# rejestrator_trasy.net
KiCad netlist of a schematic drawn in Altium Designer
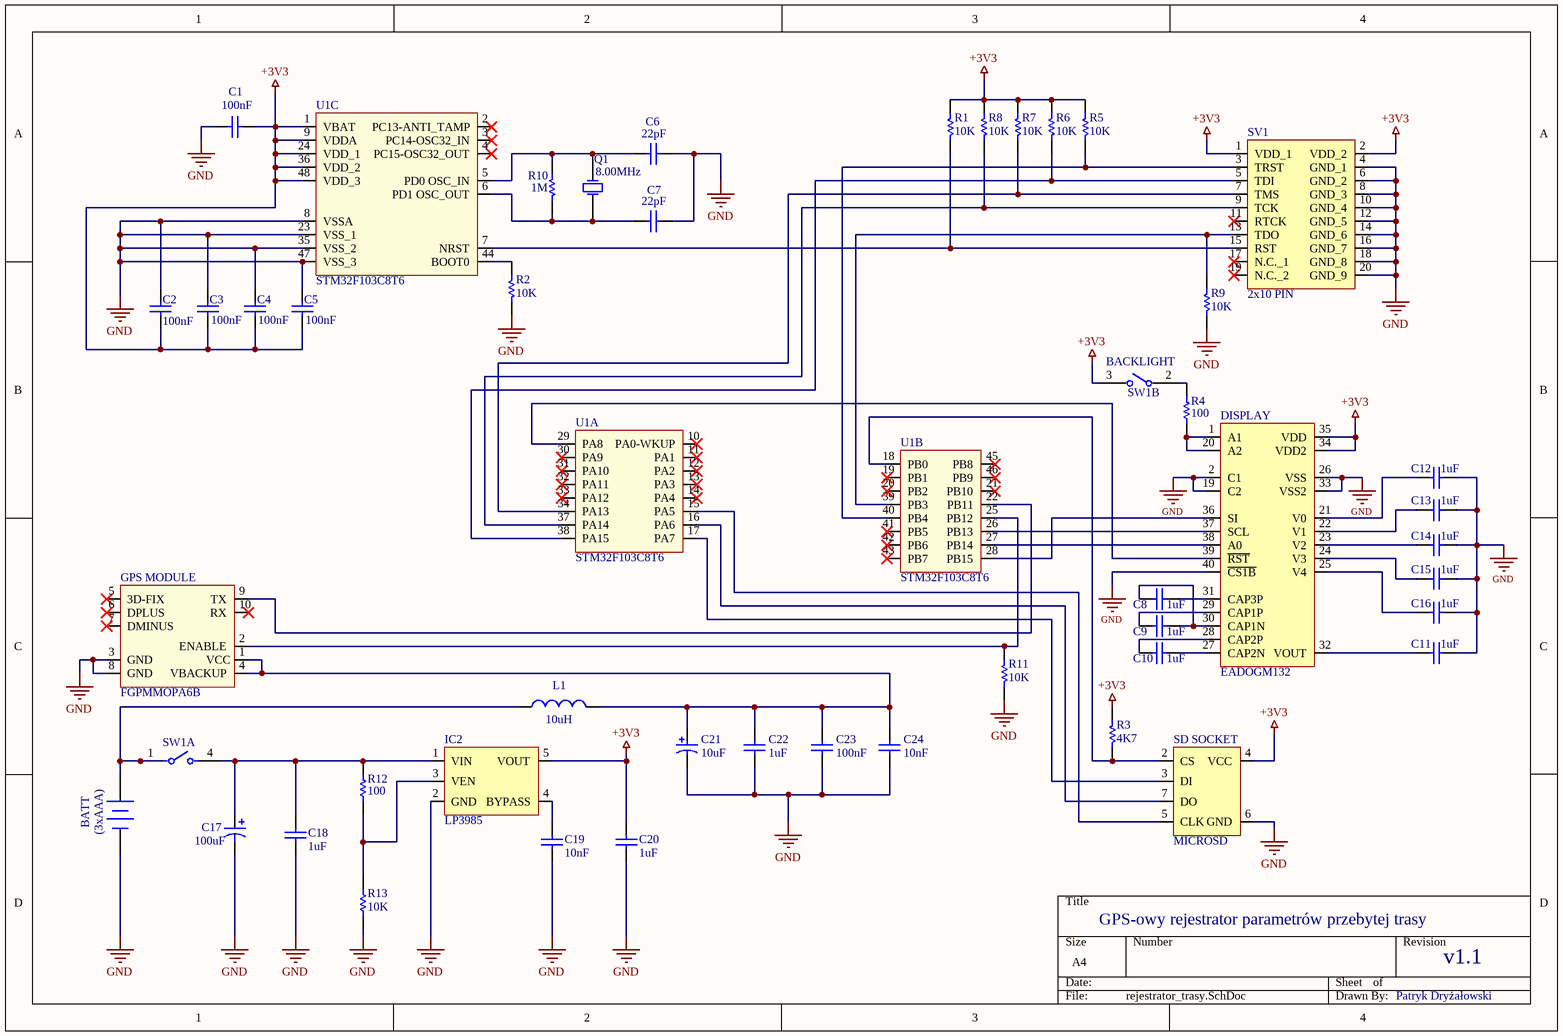
[diagram p0: rejestrator_trasy.SchDoc]

(export (version "E")
  (design (tool "Eeschema 10.0.6"))
  (components
    (comp (ref "2x10 PIN")
      (value "SV1")
      (footprint "GOLDPIN 2x10 SMD")
      (libsource (lib "PD_SCH_19Z") (part "SV1"))
    )
    (comp (ref "BATT")
      (value "(3xAAA)")
      (footprint "BAT-2")
      (description "Multicell Battery")
      (fields (field (name "PUBLISHER") "Altium Limited"))
      (libsource (lib "Miscellaneous Devices") (part "Battery"))
    )
    (comp (ref "C1")
      (value "100nF")
      (footprint "CAPC0805(2012)75_N")
      (description "CAP 100nF 25V -20% to +80% 0805 (2012 Metric) Thickness 0.75mm SMD")
      (fields (field (name "TOLERANCE") "-20% to +80%") (field (name "Comment") "CAP 100nF 25V 0805(2012)"))
      (libsource (lib "Altium Content Vault") (part "CAP"))
    )
    (comp (ref "C2")
      (value "100nF")
      (footprint "CAPC0805(2012)75_N")
      (description "CAP 100nF 25V -20% to +80% 0805 (2012 Metric) Thickness 0.75mm SMD")
      (fields (field (name "TOLERANCE") "-20% to +80%") (field (name "Comment") "CAP 100nF 25V 0805(2012)"))
      (libsource (lib "Altium Content Vault") (part "CAP"))
    )
    (comp (ref "C3")
      (value "100nF")
      (footprint "CAPC0805(2012)75_N")
      (description "CAP 100nF 25V -20% to +80% 0805 (2012 Metric) Thickness 0.75mm SMD")
      (fields (field (name "TOLERANCE") "-20% to +80%") (field (name "Comment") "CAP 100nF 25V 0805(2012)"))
      (libsource (lib "Altium Content Vault") (part "CAP"))
    )
    (comp (ref "C4")
      (value "100nF")
      (footprint "CAPC0805(2012)75_N")
      (description "CAP 100nF 25V -20% to +80% 0805 (2012 Metric) Thickness 0.75mm SMD")
      (fields (field (name "TOLERANCE") "-20% to +80%") (field (name "Comment") "CAP 100nF 25V 0805(2012)"))
      (libsource (lib "Altium Content Vault") (part "CAP"))
    )
    (comp (ref "C5")
      (value "100nF")
      (footprint "CAPC0805(2012)75_N")
      (description "CAP 100nF 25V -20% to +80% 0805 (2012 Metric) Thickness 0.75mm SMD")
      (fields (field (name "TOLERANCE") "-20% to +80%") (field (name "Comment") "CAP 100nF 25V 0805(2012)"))
      (libsource (lib "Altium Content Vault") (part "CAP"))
    )
    (comp (ref "C6")
      (value "22pF")
      (footprint "CAPC0805(2012)100_M")
      (description "CAP 22pF 10V ±20% 0805 (2012 Metric) Thickness 1mm SMD")
      (fields (field (name "TOLERANCE") "Â±20%") (field (name "Comment") "CAP 22pF 10V 0805(2012)"))
      (libsource (lib "Altium Content Vault") (part "CAP"))
    )
    (comp (ref "C7")
      (value "22pF")
      (footprint "CAPC0805(2012)100_M")
      (description "CAP 22pF 10V ±20% 0805 (2012 Metric) Thickness 1mm SMD")
      (fields (field (name "TOLERANCE") "Â±20%") (field (name "Comment") "CAP 22pF 10V 0805(2012)"))
      (libsource (lib "Altium Content Vault") (part "CAP"))
    )
    (comp (ref "C8")
      (value "1uF")
      (footprint "CAPC0805(2012)145_M")
      (description "CAP 1uF 10V ±20% 0805 (2012 Metric) Thickness 1.45mm SMD")
      (fields (field (name "TOLERANCE") "Â±20%") (field (name "Comment") "CAP 1uF 10V 0805(2012)"))
      (libsource (lib "Altium Content Vault") (part "CAP"))
    )
    (comp (ref "C9")
      (value "1uF")
      (footprint "CAPC0805(2012)145_M")
      (description "CAP 1uF 10V ±20% 0805 (2012 Metric) Thickness 1.45mm SMD")
      (fields (field (name "TOLERANCE") "Â±20%") (field (name "Comment") "CAP 1uF 10V 0805(2012)"))
      (libsource (lib "Altium Content Vault") (part "CAP"))
    )
    (comp (ref "C10")
      (value "1uF")
      (footprint "CAPC0805(2012)145_M")
      (description "CAP 1uF 10V ±20% 0805 (2012 Metric) Thickness 1.45mm SMD")
      (fields (field (name "TOLERANCE") "Â±20%") (field (name "Comment") "CAP 1uF 10V 0805(2012)"))
      (libsource (lib "Altium Content Vault") (part "CAP"))
    )
    (comp (ref "C11")
      (value "1uF")
      (footprint "CAPC0805(2012)145_M")
      (description "CAP 1uF 10V ±20% 0805 (2012 Metric) Thickness 1.45mm SMD")
      (fields (field (name "TOLERANCE") "Â±20%") (field (name "Comment") "CAP 1uF 10V 0805(2012)"))
      (libsource (lib "Altium Content Vault") (part "CAP"))
    )
    (comp (ref "C12")
      (value "1uF")
      (footprint "CAPC0805(2012)145_M")
      (description "CAP 1uF 10V ±20% 0805 (2012 Metric) Thickness 1.45mm SMD")
      (fields (field (name "TOLERANCE") "Â±20%") (field (name "Comment") "CAP 1uF 10V 0805(2012)"))
      (libsource (lib "Altium Content Vault") (part "CAP"))
    )
    (comp (ref "C13")
      (value "1uF")
      (footprint "CAPC0805(2012)145_M")
      (description "CAP 1uF 10V ±20% 0805 (2012 Metric) Thickness 1.45mm SMD")
      (fields (field (name "TOLERANCE") "Â±20%") (field (name "Comment") "CAP 1uF 10V 0805(2012)"))
      (libsource (lib "Altium Content Vault") (part "CAP"))
    )
    (comp (ref "C14")
      (value "1uF")
      (footprint "CAPC0805(2012)145_M")
      (description "CAP 1uF 10V ±20% 0805 (2012 Metric) Thickness 1.45mm SMD")
      (fields (field (name "TOLERANCE") "Â±20%") (field (name "Comment") "CAP 1uF 10V 0805(2012)"))
      (libsource (lib "Altium Content Vault") (part "CAP"))
    )
    (comp (ref "C15")
      (value "1uF")
      (footprint "CAPC0805(2012)145_M")
      (description "CAP 1uF 10V ±20% 0805 (2012 Metric) Thickness 1.45mm SMD")
      (fields (field (name "TOLERANCE") "Â±20%") (field (name "Comment") "CAP 1uF 10V 0805(2012)"))
      (libsource (lib "Altium Content Vault") (part "CAP"))
    )
    (comp (ref "C16")
      (value "1uF")
      (footprint "CAPC0805(2012)145_M")
      (description "CAP 1uF 10V ±20% 0805 (2012 Metric) Thickness 1.45mm SMD")
      (fields (field (name "TOLERANCE") "Â±20%") (field (name "Comment") "CAP 1uF 10V 0805(2012)"))
      (libsource (lib "Altium Content Vault") (part "CAP"))
    )
    (comp (ref "C17")
      (value "100uF")
      (footprint "C0805")
      (description "Polarized Capacitor (Surface Mount)")
      (fields (field (name "Comment") "Cap Pol3") (field (name "PUBLISHER") "Altium Limited"))
      (libsource (lib "Miscellaneous Devices") (part "Cap Pol3"))
    )
    (comp (ref "C18")
      (value "1uF")
      (footprint "CAPC0805(2012)145_M")
      (description "CAP 1uF 10V ±20% 0805 (2012 Metric) Thickness 1.45mm SMD")
      (fields (field (name "TOLERANCE") "Â±20%") (field (name "Comment") "CAP 1uF 10V 0805(2012)"))
      (libsource (lib "Altium Content Vault") (part "CAP"))
    )
    (comp (ref "C19")
      (value "10nF")
      (footprint "CAPC0805(2012)75_N")
      (description "CAP 10nF 16V ±20% 0805 (2012 Metric) Thickness 0.75mm SMD")
      (fields (field (name "TOLERANCE") "Â±20%") (field (name "Comment") "CAP 10nF 16V 0805(2012)"))
      (libsource (lib "Altium Content Vault") (part "CAP"))
    )
    (comp (ref "C20")
      (value "1uF")
      (footprint "CAPC0805(2012)145_M")
      (description "CAP 1uF 10V ±20% 0805 (2012 Metric) Thickness 1.45mm SMD")
      (fields (field (name "TOLERANCE") "Â±20%") (field (name "Comment") "CAP 1uF 10V 0805(2012)"))
      (libsource (lib "Altium Content Vault") (part "CAP"))
    )
    (comp (ref "C21")
      (value "ECA1HM100")
      (footprint "CAPPR55-200-1100X500X1200")
      (description "Aluminum Electrolytic Capacitor, 10 uF, +/- 20%, 50 V, -40 to 85 degC, 2-Pin THD, RoHS, Bulk")
      (fields
        (field (name "MANUFACTURER") "Panasonic")
        (field (name "CAPACITANCE") "10uF")
        (field (name "TOLERANCE") "20%")
      )
      (libsource (lib "Altium Content Vault") (part "CAP-P-2"))
    )
    (comp (ref "C22")
      (value "1uF")
      (footprint "CAPC0805(2012)145_M")
      (description "CAP 1uF 10V ±20% 0805 (2012 Metric) Thickness 1.45mm SMD")
      (fields (field (name "TOLERANCE") "Â±20%") (field (name "Comment") "CAP 1uF 10V 0805(2012)"))
      (libsource (lib "Altium Content Vault") (part "CAP"))
    )
    (comp (ref "C23")
      (value "100nF")
      (footprint "CAPC0805(2012)75_N")
      (description "CAP 100nF 25V -20% to +80% 0805 (2012 Metric) Thickness 0.75mm SMD")
      (fields (field (name "TOLERANCE") "-20% to +80%") (field (name "Comment") "CAP 100nF 25V 0805(2012)"))
      (libsource (lib "Altium Content Vault") (part "CAP"))
    )
    (comp (ref "C24")
      (value "10nF")
      (footprint "CAPC0805(2012)75_N")
      (description "CAP 10nF 16V ±20% 0805 (2012 Metric) Thickness 0.75mm SMD")
      (fields (field (name "TOLERANCE") "Â±20%") (field (name "Comment") "CAP 10nF 16V 0805(2012)"))
      (libsource (lib "Altium Content Vault") (part "CAP"))
    )
    (comp (ref "DISPLAY")
      (value "EADOGM132")
      (footprint "EA DOGM132")
      (libsource (lib "PD_SCH_19Z") (part "EA DOGM132"))
    )
    (comp (ref "GPS MODULE")
      (value "FGPMMOPA6B")
      (footprint "GTPA010")
      (libsource (lib "PD_SCH_19Z") (part "FGPMMOPA6B"))
    )
    (comp (ref "IC2") (value "LP3985") (footprint "SOT-23") (libsource (lib "PD_SCH_19Z") (part "LP3985")))
    (comp (ref "L1")
      (value "BRC2012T2R2MD")
      (footprint "INDC2013X140X50LL20T20")
      (fields
        (field (name "TOLERANCE") "±20%")
        (field (name "INDUCTANCE") "10uH")
        (field (name "MANUFACTURER") "Taiyo Yuden")
      )
      (libsource (lib "Altium Content Vault") (part "IND-2"))
    )
    (comp (ref "Q1")
      (value "Quartz")
      (footprint "TXC-9C-2_V")
      (fields
        (field (name "PARTNUMBER") "9C-3.6864MBBK-T")
        (field (name "MANUFACTURER") "TXC")
        (field (name "FREQUENCY") "8.00MHz")
      )
      (libsource (lib "Altium Content Vault") (part "TXC-XTAL_1-2-2"))
    )
    (comp (ref "R1")
      (value "10K")
      (footprint "RESC0805(2012)_L")
      (description "10K 0.125W 5% 0805 (2012 Metric)  SMD")
      (fields (field (name "POWER") "0.125 W") (field (name "TOLERANCE") "5 %"))
      (libsource (lib "Altium Content Vault") (part "RES"))
    )
    (comp (ref "R2")
      (value "10K")
      (footprint "RESC0805(2012)_L")
      (description "10K 0.125W 5% 0805 (2012 Metric)  SMD")
      (fields (field (name "POWER") "0.125 W") (field (name "TOLERANCE") "5 %"))
      (libsource (lib "Altium Content Vault") (part "RES"))
    )
    (comp (ref "R3")
      (value "4K7")
      (footprint "RESC0805(2012)_N")
      (description "4K7 0.125W 5% 0805 (2012 Metric)  SMD")
      (fields (field (name "POWER") "0.125 W") (field (name "TOLERANCE") "5 %"))
      (libsource (lib "Altium Content Vault") (part "RES"))
    )
    (comp (ref "R4")
      (value "100")
      (footprint "RESC0805(2012)_M")
      (description "100R 0.125W 5% 0805 (2012 Metric)  SMD")
      (fields (field (name "TOLERANCE") "5 %") (field (name "POWER") "0.125 W"))
      (libsource (lib "Altium Content Vault") (part "RES"))
    )
    (comp (ref "R5")
      (value "10K")
      (footprint "RESC0805(2012)_L")
      (description "10K 0.125W 5% 0805 (2012 Metric)  SMD")
      (fields (field (name "POWER") "0.125 W") (field (name "TOLERANCE") "5 %"))
      (libsource (lib "Altium Content Vault") (part "RES"))
    )
    (comp (ref "R6")
      (value "10K")
      (footprint "RESC0805(2012)_L")
      (description "10K 0.125W 5% 0805 (2012 Metric)  SMD")
      (fields (field (name "POWER") "0.125 W") (field (name "TOLERANCE") "5 %"))
      (libsource (lib "Altium Content Vault") (part "RES"))
    )
    (comp (ref "R7")
      (value "10K")
      (footprint "RESC0805(2012)_L")
      (description "10K 0.125W 5% 0805 (2012 Metric)  SMD")
      (fields (field (name "POWER") "0.125 W") (field (name "TOLERANCE") "5 %"))
      (libsource (lib "Altium Content Vault") (part "RES"))
    )
    (comp (ref "R8")
      (value "10K")
      (footprint "RESC0805(2012)_L")
      (description "10K 0.125W 5% 0805 (2012 Metric)  SMD")
      (fields (field (name "POWER") "0.125 W") (field (name "TOLERANCE") "5 %"))
      (libsource (lib "Altium Content Vault") (part "RES"))
    )
    (comp (ref "R9")
      (value "10K")
      (footprint "RESC0805(2012)_L")
      (description "10K 0.125W 5% 0805 (2012 Metric)  SMD")
      (fields (field (name "POWER") "0.125 W") (field (name "TOLERANCE") "5 %"))
      (libsource (lib "Altium Content Vault") (part "RES"))
    )
    (comp (ref "R10")
      (value "1M")
      (footprint "RESC0805(2012)_L")
      (description "1M 0.125W 5% 0805 (2012 Metric)  SMD")
      (fields (field (name "TOLERANCE") "5 %") (field (name "POWER") "0.125 W"))
      (libsource (lib "Altium Content Vault") (part "RES"))
    )
    (comp (ref "R11")
      (value "10K")
      (footprint "RESC0805(2012)_L")
      (description "10K 0.125W 5% 0805 (2012 Metric)  SMD")
      (fields (field (name "POWER") "0.125 W") (field (name "TOLERANCE") "5 %"))
      (libsource (lib "Altium Content Vault") (part "RES"))
    )
    (comp (ref "R12")
      (value "100")
      (footprint "RESC0805(2012)_M")
      (description "100R 0.125W 5% 0805 (2012 Metric)  SMD")
      (fields (field (name "TOLERANCE") "5 %") (field (name "POWER") "0.125 W"))
      (libsource (lib "Altium Content Vault") (part "RES"))
    )
    (comp (ref "R13")
      (value "10K")
      (footprint "RESC0805(2012)_L")
      (description "10K 0.125W 5% 0805 (2012 Metric)  SMD")
      (fields (field (name "POWER") "0.125 W") (field (name "TOLERANCE") "5 %"))
      (libsource (lib "Altium Content Vault") (part "RES"))
    )
    (comp (ref "SD SOCKET")
      (value "MICROSD")
      (footprint "SD CONN")
      (libsource (lib "PD_SCH_19Z") (part "MICROSD"))
    )
    (comp (ref "SW1")
      (value "1825057-1")
      (footprint "TE_Connectivity_1825057-1_MFG")
      (description "SWITCH SLIDE DIP SPST 100MA 24V")
      (fields (field (name "PART NUMBER") "1825057-1") (field (name "MANUFACTURER") "TE Connectivity"))
      (libsource (lib "Altium Content Vault") (part "1825057-1"))
    )
    (comp (ref "U1")
      (value "STM32F103C8T6")
      (footprint "LQFP48")
      (libsource (lib "") (part "STM32F103C8T6_2"))
    )
  )
  (nets
    (net (code "1") (name "+3V3") (class "Default")
      (node (ref "2x10 PIN") (pin "1") (pinfunction "VDD_1_1") (pintype "passive"))
      (node (ref "2x10 PIN") (pin "2") (pinfunction "VDD_2_2") (pintype "passive"))
      (node (ref "C1") (pin "2") (pinfunction "2_2") (pintype "passive"))
      (node (ref "C2") (pin "1") (pinfunction "1_1") (pintype "passive"))
      (node (ref "C20") (pin "2") (pinfunction "2_2") (pintype "passive"))
      (node (ref "C3") (pin "1") (pinfunction "1_1") (pintype "passive"))
      (node (ref "C4") (pin "1") (pinfunction "1_1") (pintype "passive"))
      (node (ref "C5") (pin "1") (pinfunction "1_1") (pintype "passive"))
      (node (ref "DISPLAY") (pin "34") (pinfunction "VDD2_34") (pintype "passive"))
      (node (ref "DISPLAY") (pin "35") (pinfunction "VDD_35") (pintype "passive"))
      (node (ref "IC2") (pin "5") (pinfunction "VOUT_5") (pintype "passive"))
      (node (ref "R1") (pin "2") (pinfunction "2_2") (pintype "passive"))
      (node (ref "R3") (pin "2") (pinfunction "2_2") (pintype "passive"))
      (node (ref "R5") (pin "2") (pinfunction "2_2") (pintype "passive"))
      (node (ref "R6") (pin "2") (pinfunction "2_2") (pintype "passive"))
      (node (ref "R7") (pin "2") (pinfunction "2_2") (pintype "passive"))
      (node (ref "R8") (pin "2") (pinfunction "2_2") (pintype "passive"))
      (node (ref "SD SOCKET") (pin "4") (pinfunction "VCC_4") (pintype "passive"))
      (node (ref "SW1") (pin "3") (pinfunction "3_3") (pintype "passive"))
      (node (ref "U1") (pin "1") (pinfunction "VBAT_1") (pintype "passive"))
      (node (ref "U1") (pin "24") (pinfunction "VDD_1_24") (pintype "passive"))
      (node (ref "U1") (pin "36") (pinfunction "VDD_2_36") (pintype "passive"))
      (node (ref "U1") (pin "48") (pinfunction "VDD_3_48") (pintype "passive"))
      (node (ref "U1") (pin "9") (pinfunction "VDDA_9") (pintype "passive"))
    )
    (net (code "2") (name "GND") (class "Default")
      (node (ref "2x10 PIN") (pin "10") (pinfunction "GND_4_10") (pintype "passive"))
      (node (ref "2x10 PIN") (pin "12") (pinfunction "GND_5_12") (pintype "passive"))
      (node (ref "2x10 PIN") (pin "14") (pinfunction "GND_6_14") (pintype "passive"))
      (node (ref "2x10 PIN") (pin "16") (pinfunction "GND_7_16") (pintype "passive"))
      (node (ref "2x10 PIN") (pin "18") (pinfunction "GND_8_18") (pintype "passive"))
      (node (ref "2x10 PIN") (pin "20") (pinfunction "GND_9_20") (pintype "passive"))
      (node (ref "2x10 PIN") (pin "4") (pinfunction "GND_1_4") (pintype "passive"))
      (node (ref "2x10 PIN") (pin "6") (pinfunction "GND_2_6") (pintype "passive"))
      (node (ref "2x10 PIN") (pin "8") (pinfunction "GND_3_8") (pintype "passive"))
      (node (ref "BATT") (pin "2") (pinfunction "-_2") (pintype "passive"))
      (node (ref "C1") (pin "1") (pinfunction "1_1") (pintype "passive"))
      (node (ref "C11") (pin "2") (pinfunction "2_2") (pintype "passive"))
      (node (ref "C12") (pin "2") (pinfunction "2_2") (pintype "passive"))
      (node (ref "C13") (pin "2") (pinfunction "2_2") (pintype "passive"))
      (node (ref "C14") (pin "2") (pinfunction "2_2") (pintype "passive"))
      (node (ref "C15") (pin "2") (pinfunction "2_2") (pintype "passive"))
      (node (ref "C16") (pin "2") (pinfunction "2_2") (pintype "passive"))
      (node (ref "C17") (pin "2") (pinfunction "2_2") (pintype "passive"))
      (node (ref "C18") (pin "1") (pinfunction "1_1") (pintype "passive"))
      (node (ref "C19") (pin "1") (pinfunction "1_1") (pintype "passive"))
      (node (ref "C2") (pin "2") (pinfunction "2_2") (pintype "passive"))
      (node (ref "C20") (pin "1") (pinfunction "1_1") (pintype "passive"))
      (node (ref "C21") (pin "2") (pinfunction "2_2") (pintype "passive"))
      (node (ref "C22") (pin "1") (pinfunction "1_1") (pintype "passive"))
      (node (ref "C23") (pin "1") (pinfunction "1_1") (pintype "passive"))
      (node (ref "C24") (pin "1") (pinfunction "1_1") (pintype "passive"))
      (node (ref "C3") (pin "2") (pinfunction "2_2") (pintype "passive"))
      (node (ref "C4") (pin "2") (pinfunction "2_2") (pintype "passive"))
      (node (ref "C5") (pin "2") (pinfunction "2_2") (pintype "passive"))
      (node (ref "C6") (pin "1") (pinfunction "1_1") (pintype "passive"))
      (node (ref "C7") (pin "1") (pinfunction "1_1") (pintype "passive"))
      (node (ref "DISPLAY") (pin "19") (pinfunction "C2_19") (pintype "passive"))
      (node (ref "DISPLAY") (pin "2") (pinfunction "C1_2") (pintype "passive"))
      (node (ref "DISPLAY") (pin "26") (pinfunction "VSS_26") (pintype "passive"))
      (node (ref "DISPLAY") (pin "33") (pinfunction "VSS2_33") (pintype "passive"))
      (node (ref "DISPLAY") (pin "40") (pinfunction "~{CS1B}_40") (pintype "passive"))
      (node (ref "GPS MODULE") (pin "3") (pinfunction "GND_3") (pintype "passive"))
      (node (ref "GPS MODULE") (pin "8") (pinfunction "GND_8") (pintype "passive"))
      (node (ref "IC2") (pin "2") (pinfunction "GND_2") (pintype "passive"))
      (node (ref "R11") (pin "1") (pinfunction "1_1") (pintype "passive"))
      (node (ref "R13") (pin "1") (pinfunction "1_1") (pintype "passive"))
      (node (ref "R2") (pin "1") (pinfunction "1_1") (pintype "passive"))
      (node (ref "R9") (pin "1") (pinfunction "1_1") (pintype "passive"))
      (node (ref "SD SOCKET") (pin "6") (pinfunction "GND_6") (pintype "passive"))
      (node (ref "U1") (pin "23") (pinfunction "VSS_1_23") (pintype "passive"))
      (node (ref "U1") (pin "35") (pinfunction "VSS_2_35") (pintype "passive"))
      (node (ref "U1") (pin "47") (pinfunction "VSS_3_47") (pintype "passive"))
      (node (ref "U1") (pin "8") (pinfunction "VSSA_8") (pintype "passive"))
    )
    (net (code "3") (name "Net-(2x10 PIN-RST)") (class "Default")
      (node (ref "2x10 PIN") (pin "15") (pinfunction "RST_15") (pintype "passive"))
      (node (ref "R1") (pin "1") (pinfunction "1_1") (pintype "passive"))
      (node (ref "U1") (pin "7") (pinfunction "NRST_7") (pintype "passive"))
    )
    (net (code "4") (name "Net-(2x10 PIN-TCK)") (class "Default")
      (node (ref "2x10 PIN") (pin "9") (pinfunction "TCK_9") (pintype "passive"))
      (node (ref "R8") (pin "1") (pinfunction "1_1") (pintype "passive"))
      (node (ref "U1") (pin "37") (pinfunction "PA14_37") (pintype "passive"))
    )
    (net (code "5") (name "Net-(2x10 PIN-TDI)") (class "Default")
      (node (ref "2x10 PIN") (pin "5") (pinfunction "TDI_5") (pintype "passive"))
      (node (ref "R6") (pin "1") (pinfunction "1_1") (pintype "passive"))
      (node (ref "U1") (pin "38") (pinfunction "PA15_38") (pintype "passive"))
    )
    (net (code "6") (name "Net-(2x10 PIN-TDO)") (class "Default")
      (node (ref "2x10 PIN") (pin "13") (pinfunction "TDO_13") (pintype "passive"))
      (node (ref "R9") (pin "2") (pinfunction "2_2") (pintype "passive"))
      (node (ref "U1") (pin "39") (pinfunction "PB3_39") (pintype "passive"))
    )
    (net (code "7") (name "Net-(2x10 PIN-TMS)") (class "Default")
      (node (ref "2x10 PIN") (pin "7") (pinfunction "TMS_7") (pintype "passive"))
      (node (ref "R7") (pin "1") (pinfunction "1_1") (pintype "passive"))
      (node (ref "U1") (pin "34") (pinfunction "PA13_34") (pintype "passive"))
    )
    (net (code "8") (name "Net-(2x10 PIN-TRST)") (class "Default")
      (node (ref "2x10 PIN") (pin "3") (pinfunction "TRST_3") (pintype "passive"))
      (node (ref "R5") (pin "1") (pinfunction "1_1") (pintype "passive"))
      (node (ref "U1") (pin "40") (pinfunction "PB4_40") (pintype "passive"))
    )
    (net (code "9") (name "Net-(BATT-+)") (class "Default")
      (node (ref "BATT") (pin "1") (pinfunction "+_1") (pintype "passive"))
      (node (ref "L1") (pin "1") (pinfunction "1_1") (pintype "passive"))
      (node (ref "SW1") (pin "1") (pinfunction "1_1") (pintype "passive"))
    )
    (net (code "10") (name "Net-(DISPLAY-A0)") (class "Default")
      (node (ref "DISPLAY") (pin "38") (pinfunction "A0_38") (pintype "passive"))
      (node (ref "U1") (pin "27") (pinfunction "PB14_27") (pintype "passive"))
    )
    (net (code "11") (name "Net-(DISPLAY-A1)") (class "Default")
      (node (ref "DISPLAY") (pin "1") (pinfunction "A1_1") (pintype "passive"))
      (node (ref "DISPLAY") (pin "20") (pinfunction "A2_20") (pintype "passive"))
      (node (ref "R4") (pin "1") (pinfunction "1_1") (pintype "passive"))
    )
    (net (code "12") (name "Net-(DISPLAY-CAP1N)") (class "Default")
      (node (ref "C8") (pin "1") (pinfunction "1_1") (pintype "passive"))
      (node (ref "C9") (pin "2") (pinfunction "2_2") (pintype "passive"))
      (node (ref "DISPLAY") (pin "30") (pinfunction "CAP1N_30") (pintype "passive"))
    )
    (net (code "13") (name "Net-(DISPLAY-CAP1P)") (class "Default")
      (node (ref "C9") (pin "1") (pinfunction "1_1") (pintype "passive"))
      (node (ref "DISPLAY") (pin "29") (pinfunction "CAP1P_29") (pintype "passive"))
    )
    (net (code "14") (name "Net-(DISPLAY-CAP2N)") (class "Default")
      (node (ref "C10") (pin "2") (pinfunction "2_2") (pintype "passive"))
      (node (ref "DISPLAY") (pin "27") (pinfunction "CAP2N_27") (pintype "passive"))
    )
    (net (code "15") (name "Net-(DISPLAY-CAP2P)") (class "Default")
      (node (ref "C10") (pin "1") (pinfunction "1_1") (pintype "passive"))
      (node (ref "DISPLAY") (pin "28") (pinfunction "CAP2P_28") (pintype "passive"))
    )
    (net (code "16") (name "Net-(DISPLAY-CAP3P)") (class "Default")
      (node (ref "C8") (pin "2") (pinfunction "2_2") (pintype "passive"))
      (node (ref "DISPLAY") (pin "31") (pinfunction "CAP3P_31") (pintype "passive"))
    )
    (net (code "17") (name "Net-(DISPLAY-SCL)") (class "Default")
      (node (ref "DISPLAY") (pin "37") (pinfunction "SCL_37") (pintype "passive"))
      (node (ref "U1") (pin "26") (pinfunction "PB13_26") (pintype "passive"))
    )
    (net (code "18") (name "Net-(DISPLAY-SI)") (class "Default")
      (node (ref "DISPLAY") (pin "36") (pinfunction "SI_36") (pintype "passive"))
      (node (ref "U1") (pin "28") (pinfunction "PB15_28") (pintype "passive"))
    )
    (net (code "19") (name "Net-(DISPLAY-V0)") (class "Default")
      (node (ref "C12") (pin "1") (pinfunction "1_1") (pintype "passive"))
      (node (ref "DISPLAY") (pin "21") (pinfunction "V0_21") (pintype "passive"))
    )
    (net (code "20") (name "Net-(DISPLAY-V1)") (class "Default")
      (node (ref "C13") (pin "1") (pinfunction "1_1") (pintype "passive"))
      (node (ref "DISPLAY") (pin "22") (pinfunction "V1_22") (pintype "passive"))
    )
    (net (code "21") (name "Net-(DISPLAY-V2)") (class "Default")
      (node (ref "C14") (pin "1") (pinfunction "1_1") (pintype "passive"))
      (node (ref "DISPLAY") (pin "23") (pinfunction "V2_23") (pintype "passive"))
    )
    (net (code "22") (name "Net-(DISPLAY-V3)") (class "Default")
      (node (ref "C15") (pin "1") (pinfunction "1_1") (pintype "passive"))
      (node (ref "DISPLAY") (pin "24") (pinfunction "V3_24") (pintype "passive"))
    )
    (net (code "23") (name "Net-(DISPLAY-V4)") (class "Default")
      (node (ref "C16") (pin "1") (pinfunction "1_1") (pintype "passive"))
      (node (ref "DISPLAY") (pin "25") (pinfunction "V4_25") (pintype "passive"))
    )
    (net (code "24") (name "Net-(DISPLAY-VOUT)") (class "Default")
      (node (ref "C11") (pin "1") (pinfunction "1_1") (pintype "passive"))
      (node (ref "DISPLAY") (pin "32") (pinfunction "VOUT_32") (pintype "passive"))
    )
    (net (code "25") (name "Net-(DISPLAY-~{RST})") (class "Default")
      (node (ref "DISPLAY") (pin "39") (pinfunction "~{RST}_39") (pintype "passive"))
      (node (ref "U1") (pin "29") (pinfunction "PA8_29") (pintype "passive"))
    )
    (net (code "26") (name "Net-(GPS MODULE-ENABLE)") (class "Default")
      (node (ref "GPS MODULE") (pin "2") (pinfunction "ENABLE_2") (pintype "passive"))
      (node (ref "R11") (pin "2") (pinfunction "2_2") (pintype "passive"))
      (node (ref "U1") (pin "25") (pinfunction "PB12_25") (pintype "passive"))
    )
    (net (code "27") (name "Net-(GPS MODULE-TX)") (class "Default")
      (node (ref "GPS MODULE") (pin "9") (pinfunction "TX_9") (pintype "passive"))
      (node (ref "U1") (pin "22") (pinfunction "PB11_22") (pintype "passive"))
    )
    (net (code "28") (name "Net-(GPS MODULE-VBACKUP)") (class "Default")
      (node (ref "C21") (pin "1") (pinfunction "1_1") (pintype "passive"))
      (node (ref "C22") (pin "2") (pinfunction "2_2") (pintype "passive"))
      (node (ref "C23") (pin "2") (pinfunction "2_2") (pintype "passive"))
      (node (ref "C24") (pin "2") (pinfunction "2_2") (pintype "passive"))
      (node (ref "GPS MODULE") (pin "1") (pinfunction "VCC_1") (pintype "passive"))
      (node (ref "GPS MODULE") (pin "4") (pinfunction "VBACKUP_4") (pintype "passive"))
      (node (ref "L1") (pin "2") (pinfunction "2_2") (pintype "passive"))
    )
    (net (code "29") (name "Net-(IC2-BYPASS)") (class "Default")
      (node (ref "C19") (pin "2") (pinfunction "2_2") (pintype "passive"))
      (node (ref "IC2") (pin "4") (pinfunction "BYPASS_4") (pintype "passive"))
    )
    (net (code "30") (name "Net-(IC2-VEN)") (class "Default")
      (node (ref "IC2") (pin "3") (pinfunction "VEN_3") (pintype "passive"))
      (node (ref "R12") (pin "1") (pinfunction "1_1") (pintype "passive"))
      (node (ref "R13") (pin "2") (pinfunction "2_2") (pintype "passive"))
    )
    (net (code "31") (name "Net-(IC2-VIN)") (class "Default")
      (node (ref "C17") (pin "1") (pinfunction "1_1") (pintype "passive"))
      (node (ref "C18") (pin "2") (pinfunction "2_2") (pintype "passive"))
      (node (ref "IC2") (pin "1") (pinfunction "VIN_1") (pintype "passive"))
      (node (ref "R12") (pin "2") (pinfunction "2_2") (pintype "passive"))
      (node (ref "SW1") (pin "4") (pinfunction "4_4") (pintype "passive"))
    )
    (net (code "32") (name "Net-(Q1-X1)") (class "Default")
      (node (ref "C6") (pin "2") (pinfunction "2_2") (pintype "passive"))
      (node (ref "Q1") (pin "1") (pinfunction "X1_1") (pintype "passive"))
      (node (ref "R10") (pin "2") (pinfunction "2_2") (pintype "passive"))
      (node (ref "U1") (pin "5") (pinfunction "PD0_OSC_IN_5") (pintype "passive"))
    )
    (net (code "33") (name "Net-(Q1-X2)") (class "Default")
      (node (ref "C7") (pin "2") (pinfunction "2_2") (pintype "passive"))
      (node (ref "Q1") (pin "2") (pinfunction "X2_2") (pintype "passive"))
      (node (ref "R10") (pin "1") (pinfunction "1_1") (pintype "passive"))
      (node (ref "U1") (pin "6") (pinfunction "PD1_OSC_OUT_6") (pintype "passive"))
    )
    (net (code "34") (name "Net-(R4-Pad2)") (class "Default")
      (node (ref "R4") (pin "2") (pinfunction "2_2") (pintype "passive"))
      (node (ref "SW1") (pin "2") (pinfunction "2_2") (pintype "passive"))
    )
    (net (code "35") (name "Net-(SD SOCKET-CLK)") (class "Default")
      (node (ref "SD SOCKET") (pin "5") (pinfunction "CLK_5") (pintype "passive"))
      (node (ref "U1") (pin "15") (pinfunction "PA5_15") (pintype "passive"))
    )
    (net (code "36") (name "Net-(SD SOCKET-CS)") (class "Default")
      (node (ref "R3") (pin "1") (pinfunction "1_1") (pintype "passive"))
      (node (ref "SD SOCKET") (pin "2") (pinfunction "CS_2") (pintype "passive"))
      (node (ref "U1") (pin "18") (pinfunction "PB0_18") (pintype "passive"))
    )
    (net (code "37") (name "Net-(SD SOCKET-DI)") (class "Default")
      (node (ref "SD SOCKET") (pin "3") (pinfunction "DI_3") (pintype "passive"))
      (node (ref "U1") (pin "17") (pinfunction "PA7_17") (pintype "passive"))
    )
    (net (code "38") (name "Net-(SD SOCKET-DO)") (class "Default")
      (node (ref "SD SOCKET") (pin "7") (pinfunction "DO_7") (pintype "passive"))
      (node (ref "U1") (pin "16") (pinfunction "PA6_16") (pintype "passive"))
    )
    (net (code "39") (name "Net-(U1C-BOOT0)") (class "Default")
      (node (ref "R2") (pin "2") (pinfunction "2_2") (pintype "passive"))
      (node (ref "U1") (pin "44") (pinfunction "BOOT0_44") (pintype "passive"))
    )
    (net (code "40") (name "unconnected-(2x10 PIN-N.C._1-Pad17)") (class "Default")
      (node (ref "2x10 PIN") (pin "17") (pinfunction "N.C._1_17") (pintype "passive+no_connect"))
    )
    (net (code "41") (name "unconnected-(2x10 PIN-N.C._2-Pad19)") (class "Default")
      (node (ref "2x10 PIN") (pin "19") (pinfunction "N.C._2_19") (pintype "passive+no_connect"))
    )
    (net (code "42") (name "unconnected-(2x10 PIN-RTCK-Pad11)") (class "Default")
      (node (ref "2x10 PIN") (pin "11") (pinfunction "RTCK_11") (pintype "passive+no_connect"))
    )
    (net (code "43") (name "unconnected-(GPS MODULE-3D-FIX-Pad5)") (class "Default")
      (node (ref "GPS MODULE") (pin "5") (pinfunction "3D-FIX_5") (pintype "passive+no_connect"))
    )
    (net (code "44") (name "unconnected-(GPS MODULE-DMINUS-Pad7)") (class "Default")
      (node (ref "GPS MODULE") (pin "7") (pinfunction "DMINUS_7") (pintype "passive+no_connect"))
    )
    (net (code "45") (name "unconnected-(GPS MODULE-DPLUS-Pad6)") (class "Default")
      (node (ref "GPS MODULE") (pin "6") (pinfunction "DPLUS_6") (pintype "passive+no_connect"))
    )
    (net (code "46") (name "unconnected-(GPS MODULE-RX-Pad10)") (class "Default")
      (node (ref "GPS MODULE") (pin "10") (pinfunction "RX_10") (pintype "passive+no_connect"))
    )
    (net (code "47") (name "unconnected-(U1A-PA0-WKUP-Pad10)") (class "Default")
      (node (ref "U1") (pin "10") (pinfunction "PA0-WKUP_10") (pintype "passive+no_connect"))
    )
    (net (code "48") (name "unconnected-(U1A-PA1-Pad11)") (class "Default")
      (node (ref "U1") (pin "11") (pinfunction "PA1_11") (pintype "passive+no_connect"))
    )
    (net (code "49") (name "unconnected-(U1A-PA2-Pad12)") (class "Default")
      (node (ref "U1") (pin "12") (pinfunction "PA2_12") (pintype "passive+no_connect"))
    )
    (net (code "50") (name "unconnected-(U1A-PA3-Pad13)") (class "Default")
      (node (ref "U1") (pin "13") (pinfunction "PA3_13") (pintype "passive+no_connect"))
    )
    (net (code "51") (name "unconnected-(U1A-PA4-Pad14)") (class "Default")
      (node (ref "U1") (pin "14") (pinfunction "PA4_14") (pintype "passive+no_connect"))
    )
    (net (code "52") (name "unconnected-(U1A-PA9-Pad30)") (class "Default")
      (node (ref "U1") (pin "30") (pinfunction "PA9_30") (pintype "passive+no_connect"))
    )
    (net (code "53") (name "unconnected-(U1A-PA10-Pad31)") (class "Default")
      (node (ref "U1") (pin "31") (pinfunction "PA10_31") (pintype "passive+no_connect"))
    )
    (net (code "54") (name "unconnected-(U1A-PA11-Pad32)") (class "Default")
      (node (ref "U1") (pin "32") (pinfunction "PA11_32") (pintype "passive+no_connect"))
    )
    (net (code "55") (name "unconnected-(U1A-PA12-Pad33)") (class "Default")
      (node (ref "U1") (pin "33") (pinfunction "PA12_33") (pintype "passive+no_connect"))
    )
    (net (code "56") (name "unconnected-(U1B-PB1-Pad19)") (class "Default")
      (node (ref "U1") (pin "19") (pinfunction "PB1_19") (pintype "passive+no_connect"))
    )
    (net (code "57") (name "unconnected-(U1B-PB2-Pad20)") (class "Default")
      (node (ref "U1") (pin "20") (pinfunction "PB2_20") (pintype "passive+no_connect"))
    )
    (net (code "58") (name "unconnected-(U1B-PB5-Pad41)") (class "Default")
      (node (ref "U1") (pin "41") (pinfunction "PB5_41") (pintype "passive+no_connect"))
    )
    (net (code "59") (name "unconnected-(U1B-PB6-Pad42)") (class "Default")
      (node (ref "U1") (pin "42") (pinfunction "PB6_42") (pintype "passive+no_connect"))
    )
    (net (code "60") (name "unconnected-(U1B-PB7-Pad43)") (class "Default")
      (node (ref "U1") (pin "43") (pinfunction "PB7_43") (pintype "passive+no_connect"))
    )
    (net (code "61") (name "unconnected-(U1B-PB8-Pad45)") (class "Default")
      (node (ref "U1") (pin "45") (pinfunction "PB8_45") (pintype "passive+no_connect"))
    )
    (net (code "62") (name "unconnected-(U1B-PB9-Pad46)") (class "Default")
      (node (ref "U1") (pin "46") (pinfunction "PB9_46") (pintype "passive+no_connect"))
    )
    (net (code "63") (name "unconnected-(U1B-PB10-Pad21)") (class "Default")
      (node (ref "U1") (pin "21") (pinfunction "PB10_21") (pintype "passive+no_connect"))
    )
    (net (code "64") (name "unconnected-(U1C-PC13-ANTI_TAMP-Pad2)") (class "Default")
      (node (ref "U1") (pin "2") (pinfunction "PC13-ANTI_TAMP_2") (pintype "passive+no_connect"))
    )
    (net (code "65") (name "unconnected-(U1C-PC14-OSC32_IN-Pad3)") (class "Default")
      (node (ref "U1") (pin "3") (pinfunction "PC14-OSC32_IN_3") (pintype "passive+no_connect"))
    )
    (net (code "66") (name "unconnected-(U1C-PC15-OSC32_OUT-Pad4)") (class "Default")
      (node (ref "U1") (pin "4") (pinfunction "PC15-OSC32_OUT_4") (pintype "passive+no_connect"))
    )
  )
)
